# ECG_max86150_v1_7.net
KiCad netlist of a schematic drawn in EAGLE
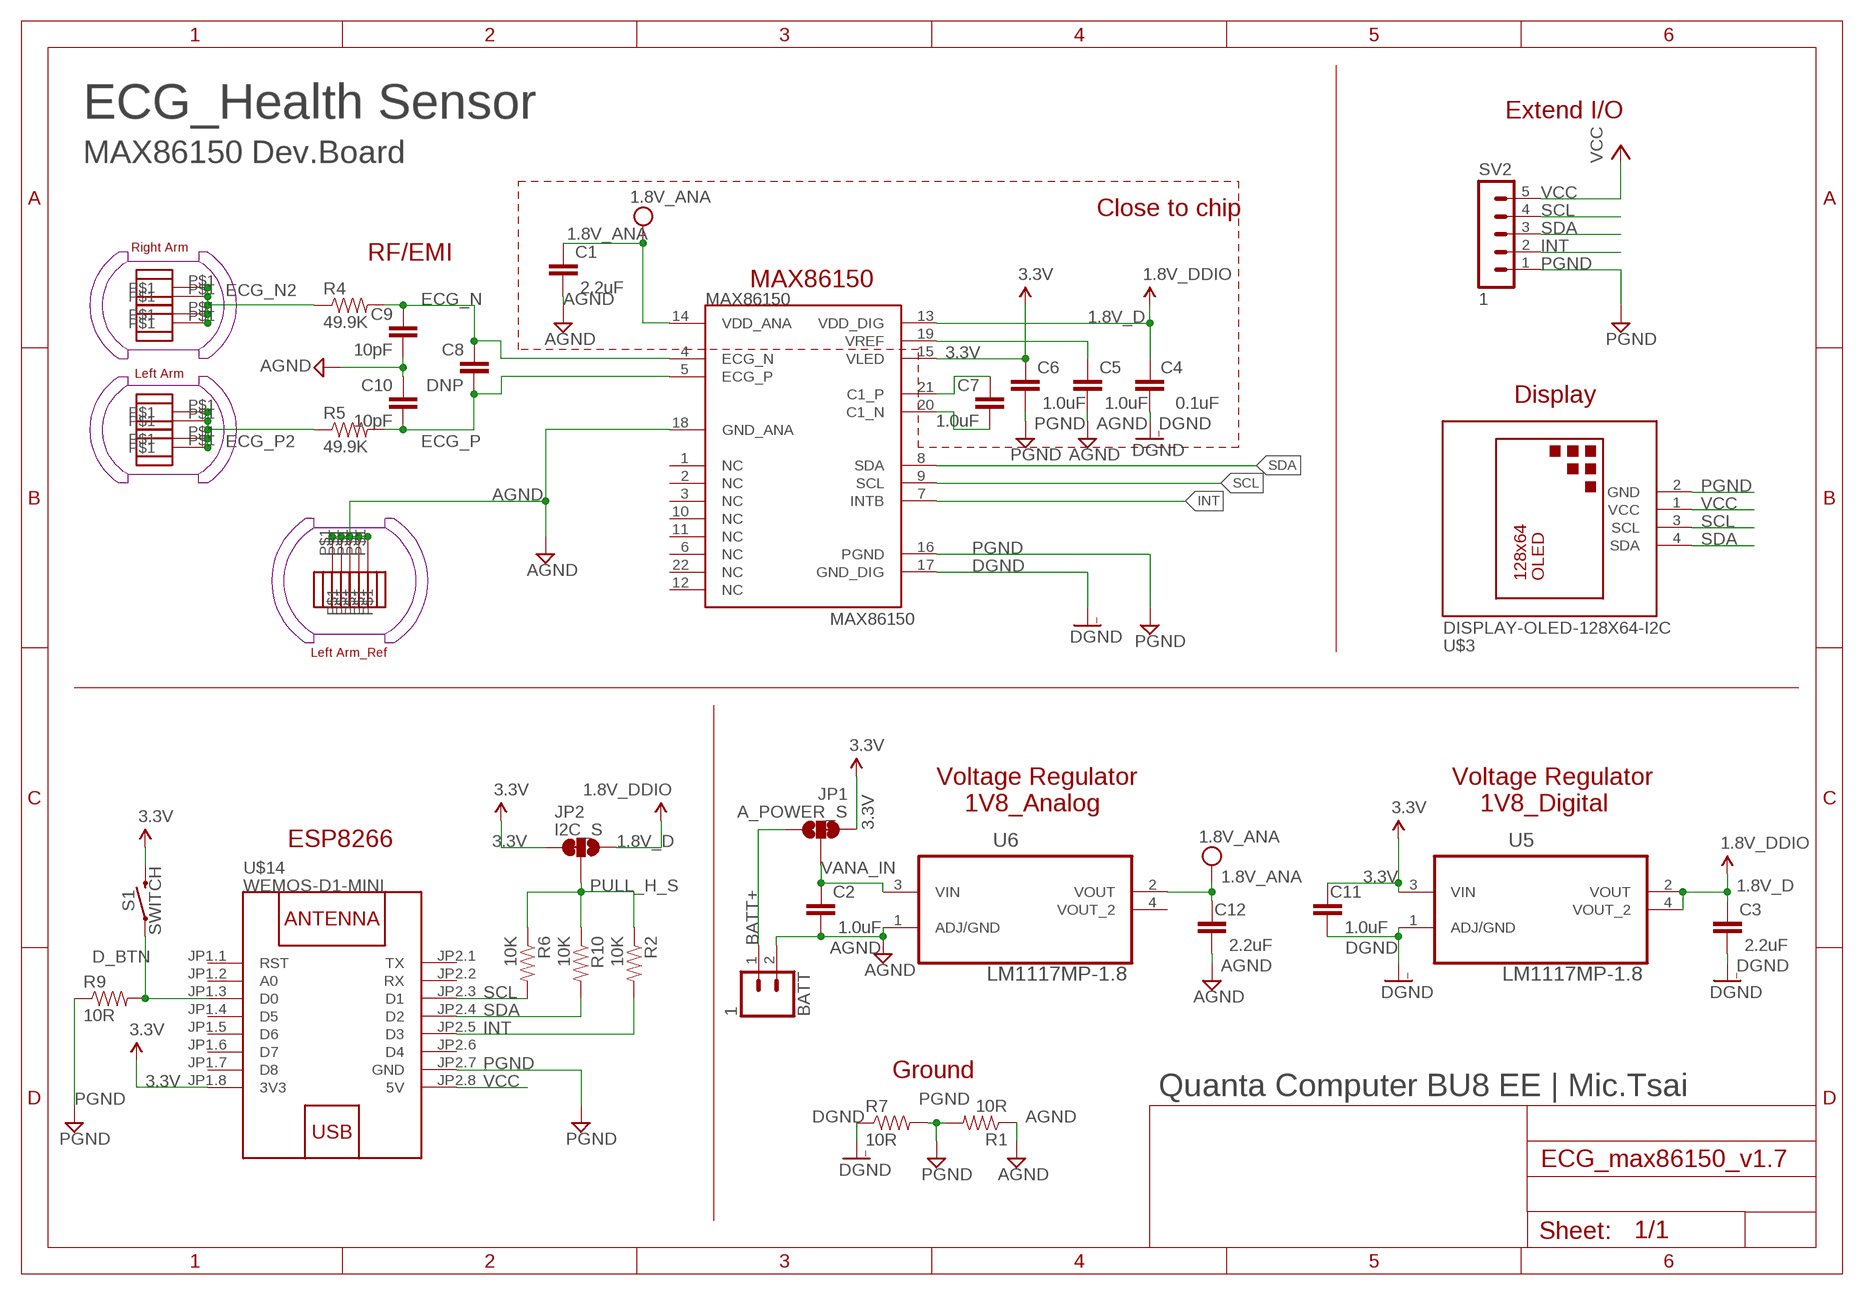
[diagram p0: schematic, sheet 1]

(export (version "E")
  (design (tool "Eeschema 10.0.6"))
  (components
    (comp (ref "BATT")
      (value "1")
      (footprint "eagle-import:1X02")
      (libsource (lib "eagle-import") (part "CONN_02"))
    )
    (comp (ref "C1")
      (value "2.2uF")
      (footprint "eagle-import:0805")
      (libsource (lib "eagle-import") (part "1.0UF-0805-25V-10%"))
    )
    (comp (ref "C2")
      (value "1.0uF")
      (footprint "eagle-import:0805")
      (libsource (lib "eagle-import") (part "1.0UF-0805-25V-10%"))
    )
    (comp (ref "C3")
      (value "2.2uF")
      (footprint "eagle-import:0805")
      (libsource (lib "eagle-import") (part "1.0UF-0805-25V-10%"))
    )
    (comp (ref "C4")
      (value "0.1uF")
      (footprint "eagle-import:0402")
      (libsource (lib "eagle-import") (part "1.0UF-0402-16V-10%"))
    )
    (comp (ref "C5")
      (value "1.0uF")
      (footprint "eagle-import:0805")
      (libsource (lib "eagle-import") (part "1.0UF-0805-25V-10%"))
    )
    (comp (ref "C6")
      (value "1.0uF")
      (footprint "eagle-import:0805")
      (libsource (lib "eagle-import") (part "1.0UF-0805-25V-10%"))
    )
    (comp (ref "C7")
      (value "1.0uF")
      (footprint "eagle-import:0805")
      (libsource (lib "eagle-import") (part "1.0UF-0805-25V-10%"))
    )
    (comp (ref "C8")
      (value "DNP")
      (footprint "eagle-import:0402")
      (libsource (lib "eagle-import") (part "1.0UF-0402-16V-10%"))
    )
    (comp (ref "C9")
      (value "10pF")
      (footprint "eagle-import:0402")
      (libsource (lib "eagle-import") (part "1.0UF-0402-16V-10%"))
    )
    (comp (ref "C10")
      (value "10pF")
      (footprint "eagle-import:0402")
      (libsource (lib "eagle-import") (part "1.0UF-0402-16V-10%"))
    )
    (comp (ref "C11")
      (value "1.0uF")
      (footprint "eagle-import:0805")
      (libsource (lib "eagle-import") (part "1.0UF-0805-25V-10%"))
    )
    (comp (ref "C12")
      (value "2.2uF")
      (footprint "eagle-import:0805")
      (libsource (lib "eagle-import") (part "1.0UF-0805-25V-10%"))
    )
    (comp (ref "JP1")
      (value "A_POWER_S")
      (footprint "eagle-import:SMT-JUMPER_3_1-NC_TRACE_SILK")
      (libsource (lib "eagle-import") (part "JUMPER-SMT_3_1-NC_TRACE_SILK"))
    )
    (comp (ref "JP2")
      (value "I2C_S")
      (footprint "eagle-import:SMT-JUMPER_3_1-NC_TRACE_SILK")
      (libsource (lib "eagle-import") (part "JUMPER-SMT_3_1-NC_TRACE_SILK"))
    )
    (comp (ref "MAX86150")
      (value "MAX86150")
      (footprint "eagle-import:MAX86150")
      (libsource (lib "eagle-import") (part "MAX86150"))
    )
    (comp (ref "R1")
      (value "10R")
      (footprint "eagle-import:0805")
      (libsource (lib "eagle-import") (part "RESISTOR0805-RES"))
    )
    (comp (ref "R2")
      (value "10K")
      (footprint "eagle-import:0402-RES")
      (libsource (lib "eagle-import") (part "RESISTOR0402-RES"))
    )
    (comp (ref "R4")
      (value "49.9K")
      (footprint "eagle-import:0402-RES")
      (libsource (lib "eagle-import") (part "RESISTOR0402-RES"))
    )
    (comp (ref "R5")
      (value "49.9K")
      (footprint "eagle-import:0402-RES")
      (libsource (lib "eagle-import") (part "RESISTOR0402-RES"))
    )
    (comp (ref "R6")
      (value "10K")
      (footprint "eagle-import:0402-RES")
      (libsource (lib "eagle-import") (part "RESISTOR0402-RES"))
    )
    (comp (ref "R7")
      (value "10R")
      (footprint "eagle-import:0805")
      (libsource (lib "eagle-import") (part "RESISTOR0805-RES"))
    )
    (comp (ref "R9")
      (value "10R")
      (footprint "eagle-import:0805")
      (libsource (lib "eagle-import") (part "RESISTOR0805-RES"))
    )
    (comp (ref "R10")
      (value "10K")
      (footprint "eagle-import:0402-RES")
      (libsource (lib "eagle-import") (part "RESISTOR0402-RES"))
    )
    (comp (ref "S1")
      (value "SWITCH")
      (footprint "eagle-import:TACTILE_SWITCH_PTH_6.0MM")
      (libsource (lib "eagle-import") (part "MOMENTARY-SWITCH-SPST-PTH-6.0MM"))
    )
    (comp (ref "SV2")
      (value "1")
      (footprint "eagle-import:MA05-1")
      (libsource (lib "eagle-import") (part "MA05-1"))
    )
    (comp (ref "U$1")
      (value "ECG_PAD")
      (footprint "eagle-import:ECG_PAD1")
      (libsource (lib "eagle-import") (part "ECG_PAD"))
    )
    (comp (ref "U$3")
      (value "DISPLAY-OLED-128X64-I2C")
      (footprint "eagle-import:DISPLAY-OLED-128X64-I2C")
      (libsource (lib "eagle-import") (part "DISPLAY-OLED-128X64-I2C"))
    )
    (comp (ref "U$4")
      (value "ECG_PAD")
      (footprint "eagle-import:ECG_PAD1")
      (libsource (lib "eagle-import") (part "ECG_PAD"))
    )
    (comp (ref "U$6")
      (value "ECG_PAD")
      (footprint "eagle-import:ECG_PAD1")
      (libsource (lib "eagle-import") (part "ECG_PAD"))
    )
    (comp (ref "U$7")
      (value "ECG_PAD")
      (footprint "eagle-import:ECG_PAD1")
      (libsource (lib "eagle-import") (part "ECG_PAD"))
    )
    (comp (ref "U$9")
      (value "ECG_PAD")
      (footprint "eagle-import:ECG_PAD1")
      (libsource (lib "eagle-import") (part "ECG_PAD"))
    )
    (comp (ref "U$10")
      (value "ECG_PAD")
      (footprint "eagle-import:ECG_PAD1")
      (libsource (lib "eagle-import") (part "ECG_PAD"))
    )
    (comp (ref "U$11")
      (value "ECG_PAD")
      (footprint "eagle-import:ECG_PAD1")
      (libsource (lib "eagle-import") (part "ECG_PAD"))
    )
    (comp (ref "U$12")
      (value "ECG_PAD")
      (footprint "eagle-import:ECG_PAD1")
      (libsource (lib "eagle-import") (part "ECG_PAD"))
    )
    (comp (ref "U$13")
      (value "ECG_PAD")
      (footprint "eagle-import:ECG_PAD1")
      (libsource (lib "eagle-import") (part "ECG_PAD"))
    )
    (comp (ref "U$14")
      (value "WEMOS-D1-MINI")
      (footprint "eagle-import:WEMOS-D1-MINI")
      (libsource (lib "eagle-import") (part "WEMOS-D1-MINI"))
    )
    (comp (ref "U$15")
      (value "ECG_PAD")
      (footprint "eagle-import:ECG_PAD1")
      (libsource (lib "eagle-import") (part "ECG_PAD"))
    )
    (comp (ref "U$16")
      (value "ECG_PAD")
      (footprint "eagle-import:ECG_PAD1")
      (libsource (lib "eagle-import") (part "ECG_PAD"))
    )
    (comp (ref "U$17")
      (value "ECG_PAD")
      (footprint "eagle-import:ECG_PAD1")
      (libsource (lib "eagle-import") (part "ECG_PAD"))
    )
    (comp (ref "U$18")
      (value "ECG_PAD")
      (footprint "eagle-import:ECG_PAD1")
      (libsource (lib "eagle-import") (part "ECG_PAD"))
    )
    (comp (ref "U5")
      (value "LM1117MP-1.8")
      (footprint "eagle-import:SOT230P696X180-4N")
      (fields (field (name "MF") "Texas Instruments") (field (name "MP") "LM1117MP-1.8/NOPB"))
      (libsource (lib "eagle-import") (part "LM1117MP-1.8"))
    )
    (comp (ref "U6")
      (value "LM1117MP-1.8")
      (footprint "eagle-import:SOT230P696X180-4N")
      (fields (field (name "MF") "Texas Instruments") (field (name "MP") "LM1117MP-1.8/NOPB"))
      (libsource (lib "eagle-import") (part "LM1117MP-1.8"))
    )
  )
  (nets
    (net (code "1") (name "/BATT+") (class "Default")
      (node (ref "BATT") (pin "1") (pinfunction "1_1") (pintype "passive"))
      (node (ref "JP1") (pin "1") (pinfunction "1_1") (pintype "passive"))
    )
    (net (code "2") (name "/D_BTN") (class "Default")
      (node (ref "R9") (pin "2") (pinfunction "2_2") (pintype "passive"))
      (node (ref "S1") (pin "1") (pinfunction "1_1") (pintype "passive"))
      (node (ref "U$14") (pin "JP1.3") (pinfunction "D0_JP1.3") (pintype "bidirectional"))
    )
    (net (code "3") (name "/ECG_N") (class "Default")
      (node (ref "C8") (pin "1") (pinfunction "1_1") (pintype "passive"))
      (node (ref "C9") (pin "1") (pinfunction "1_1") (pintype "passive"))
      (node (ref "MAX86150") (pin "4") (pinfunction "ECG_N_4") (pintype "bidirectional"))
      (node (ref "R4") (pin "2") (pinfunction "2_2") (pintype "passive"))
    )
    (net (code "4") (name "/ECG_N2") (class "Default")
      (node (ref "R4") (pin "1") (pinfunction "1_1") (pintype "passive"))
      (node (ref "U$10") (pin "P$1") (pinfunction "P$1_P$1") (pintype "bidirectional"))
      (node (ref "U$11") (pin "P$1") (pinfunction "P$1_P$1") (pintype "bidirectional"))
      (node (ref "U$16") (pin "P$1") (pinfunction "P$1_P$1") (pintype "bidirectional"))
      (node (ref "U$9") (pin "P$1") (pinfunction "P$1_P$1") (pintype "bidirectional"))
    )
    (net (code "5") (name "/ECG_P") (class "Default")
      (node (ref "C10") (pin "2") (pinfunction "2_2") (pintype "passive"))
      (node (ref "C8") (pin "2") (pinfunction "2_2") (pintype "passive"))
      (node (ref "MAX86150") (pin "5") (pinfunction "ECG_P_5") (pintype "bidirectional"))
      (node (ref "R5") (pin "2") (pinfunction "2_2") (pintype "passive"))
    )
    (net (code "6") (name "/ECG_P2") (class "Default")
      (node (ref "R5") (pin "1") (pinfunction "1_1") (pintype "passive"))
      (node (ref "U$1") (pin "P$1") (pinfunction "P$1_P$1") (pintype "bidirectional"))
      (node (ref "U$4") (pin "P$1") (pinfunction "P$1_P$1") (pintype "bidirectional"))
      (node (ref "U$6") (pin "P$1") (pinfunction "P$1_P$1") (pintype "bidirectional"))
      (node (ref "U$7") (pin "P$1") (pinfunction "P$1_P$1") (pintype "bidirectional"))
    )
    (net (code "7") (name "/PULL_H_S") (class "Default")
      (node (ref "JP2") (pin "2") (pinfunction "2_2") (pintype "passive"))
      (node (ref "R10") (pin "1") (pinfunction "1_1") (pintype "passive"))
      (node (ref "R2") (pin "1") (pinfunction "1_1") (pintype "passive"))
      (node (ref "R6") (pin "1") (pinfunction "1_1") (pintype "passive"))
    )
    (net (code "8") (name "/VANA_IN") (class "Default")
      (node (ref "C2") (pin "1") (pinfunction "1_1") (pintype "passive"))
      (node (ref "JP1") (pin "2") (pinfunction "2_2") (pintype "passive"))
      (node (ref "U6") (pin "3") (pinfunction "VIN_3") (pintype "input"))
    )
    (net (code "9") (name "1.8V_ANA") (class "Default")
      (node (ref "C1") (pin "1") (pinfunction "1_1") (pintype "passive"))
      (node (ref "C12") (pin "1") (pinfunction "1_1") (pintype "passive"))
      (node (ref "MAX86150") (pin "14") (pinfunction "VDD_ANA_14") (pintype "bidirectional"))
      (node (ref "U6") (pin "2") (pinfunction "VOUT_2") (pintype "output"))
    )
    (net (code "10") (name "1.8V_DDIO") (class "Default")
      (node (ref "C3") (pin "1") (pinfunction "1_1") (pintype "passive"))
      (node (ref "C4") (pin "1") (pinfunction "1_1") (pintype "passive"))
      (node (ref "JP2") (pin "1") (pinfunction "1_1") (pintype "passive"))
      (node (ref "MAX86150") (pin "13") (pinfunction "VDD_DIG_13") (pintype "bidirectional"))
      (node (ref "U5") (pin "2") (pinfunction "VOUT_2") (pintype "output"))
      (node (ref "U5") (pin "4") (pinfunction "VOUT_2_4") (pintype "output"))
    )
    (net (code "11") (name "3.3V") (class "Default")
      (node (ref "C11") (pin "1") (pinfunction "1_1") (pintype "passive"))
      (node (ref "C6") (pin "1") (pinfunction "1_1") (pintype "passive"))
      (node (ref "JP1") (pin "3") (pinfunction "3_3") (pintype "passive"))
      (node (ref "JP2") (pin "3") (pinfunction "3_3") (pintype "passive"))
      (node (ref "MAX86150") (pin "15") (pinfunction "VLED_15") (pintype "bidirectional"))
      (node (ref "S1") (pin "3") (pinfunction "2_3") (pintype "passive"))
      (node (ref "U$14") (pin "JP1.8") (pinfunction "3V3_JP1.8") (pintype "power_in"))
      (node (ref "U5") (pin "3") (pinfunction "VIN_3") (pintype "input"))
    )
    (net (code "12") (name "AGND") (class "Default")
      (node (ref "BATT") (pin "2") (pinfunction "2_2") (pintype "passive"))
      (node (ref "C1") (pin "2") (pinfunction "2_2") (pintype "passive"))
      (node (ref "C10") (pin "1") (pinfunction "1_1") (pintype "passive"))
      (node (ref "C12") (pin "2") (pinfunction "2_2") (pintype "passive"))
      (node (ref "C2") (pin "2") (pinfunction "2_2") (pintype "passive"))
      (node (ref "C5") (pin "2") (pinfunction "2_2") (pintype "passive"))
      (node (ref "C9") (pin "2") (pinfunction "2_2") (pintype "passive"))
      (node (ref "MAX86150") (pin "18") (pinfunction "GND_ANA_18") (pintype "bidirectional"))
      (node (ref "R1") (pin "1") (pinfunction "1_1") (pintype "passive"))
      (node (ref "U$12") (pin "P$1") (pinfunction "P$1_P$1") (pintype "bidirectional"))
      (node (ref "U$13") (pin "P$1") (pinfunction "P$1_P$1") (pintype "bidirectional"))
      (node (ref "U$15") (pin "P$1") (pinfunction "P$1_P$1") (pintype "bidirectional"))
      (node (ref "U$17") (pin "P$1") (pinfunction "P$1_P$1") (pintype "bidirectional"))
      (node (ref "U$18") (pin "P$1") (pinfunction "P$1_P$1") (pintype "bidirectional"))
      (node (ref "U6") (pin "1") (pinfunction "ADJ/GND_1") (pintype "passive"))
    )
    (net (code "13") (name "DGND") (class "Default")
      (node (ref "C11") (pin "2") (pinfunction "2_2") (pintype "passive"))
      (node (ref "C3") (pin "2") (pinfunction "2_2") (pintype "passive"))
      (node (ref "C4") (pin "2") (pinfunction "2_2") (pintype "passive"))
      (node (ref "MAX86150") (pin "17") (pinfunction "GND_DIG_17") (pintype "bidirectional"))
      (node (ref "R7") (pin "1") (pinfunction "1_1") (pintype "passive"))
      (node (ref "U5") (pin "1") (pinfunction "ADJ/GND_1") (pintype "passive"))
    )
    (net (code "14") (name "INT") (class "Default")
      (node (ref "MAX86150") (pin "7") (pinfunction "INTB_7") (pintype "bidirectional"))
      (node (ref "R2") (pin "2") (pinfunction "2_2") (pintype "passive"))
      (node (ref "SV2") (pin "2") (pinfunction "2_2") (pintype "passive"))
      (node (ref "U$14") (pin "JP2.5") (pinfunction "D3_JP2.5") (pintype "bidirectional"))
    )
    (net (code "15") (name "Net-(MAX86150-C1_N)") (class "Default")
      (node (ref "C7") (pin "2") (pinfunction "2_2") (pintype "passive"))
      (node (ref "MAX86150") (pin "20") (pinfunction "C1_N_20") (pintype "bidirectional"))
    )
    (net (code "16") (name "Net-(MAX86150-C1_P)") (class "Default")
      (node (ref "C7") (pin "1") (pinfunction "1_1") (pintype "passive"))
      (node (ref "MAX86150") (pin "21") (pinfunction "C1_P_21") (pintype "bidirectional"))
    )
    (net (code "17") (name "Net-(MAX86150-VREF)") (class "Default")
      (node (ref "C5") (pin "1") (pinfunction "1_1") (pintype "passive"))
      (node (ref "MAX86150") (pin "19") (pinfunction "VREF_19") (pintype "bidirectional"))
    )
    (net (code "18") (name "PGND") (class "Default")
      (node (ref "C6") (pin "2") (pinfunction "2_2") (pintype "passive"))
      (node (ref "MAX86150") (pin "16") (pinfunction "PGND_16") (pintype "bidirectional"))
      (node (ref "R1") (pin "2") (pinfunction "2_2") (pintype "passive"))
      (node (ref "R7") (pin "2") (pinfunction "2_2") (pintype "passive"))
      (node (ref "R9") (pin "1") (pinfunction "1_1") (pintype "passive"))
      (node (ref "SV2") (pin "1") (pinfunction "1_1") (pintype "passive"))
      (node (ref "U$14") (pin "JP2.7") (pinfunction "GND_JP2.7") (pintype "power_in"))
      (node (ref "U$3") (pin "2") (pinfunction "GND_2") (pintype "power_in"))
    )
    (net (code "19") (name "SCL") (class "Default")
      (node (ref "MAX86150") (pin "9") (pinfunction "SCL_9") (pintype "bidirectional"))
      (node (ref "R6") (pin "2") (pinfunction "2_2") (pintype "passive"))
      (node (ref "SV2") (pin "4") (pinfunction "4_4") (pintype "passive"))
      (node (ref "U$14") (pin "JP2.3") (pinfunction "D1_JP2.3") (pintype "bidirectional"))
      (node (ref "U$3") (pin "3") (pinfunction "SCL_3") (pintype "bidirectional"))
    )
    (net (code "20") (name "SDA") (class "Default")
      (node (ref "MAX86150") (pin "8") (pinfunction "SDA_8") (pintype "bidirectional"))
      (node (ref "R10") (pin "2") (pinfunction "2_2") (pintype "passive"))
      (node (ref "SV2") (pin "3") (pinfunction "3_3") (pintype "passive"))
      (node (ref "U$14") (pin "JP2.4") (pinfunction "D2_JP2.4") (pintype "bidirectional"))
      (node (ref "U$3") (pin "4") (pinfunction "SDA_4") (pintype "bidirectional"))
    )
    (net (code "21") (name "VCC") (class "Default")
      (node (ref "SV2") (pin "5") (pinfunction "5_5") (pintype "passive"))
      (node (ref "U$14") (pin "JP2.8") (pinfunction "5V_JP2.8") (pintype "power_in"))
      (node (ref "U$3") (pin "1") (pinfunction "VCC_1") (pintype "power_in"))
    )
    (net (code "22") (name "unconnected-(MAX86150-NC-Pad1)") (class "Default")
      (node (ref "MAX86150") (pin "1") (pinfunction "NC_1") (pintype "bidirectional"))
    )
    (net (code "23") (name "unconnected-(MAX86150-NC-Pad2)") (class "Default")
      (node (ref "MAX86150") (pin "2") (pinfunction "NC_2") (pintype "bidirectional"))
    )
    (net (code "24") (name "unconnected-(MAX86150-NC-Pad3)") (class "Default")
      (node (ref "MAX86150") (pin "3") (pinfunction "NC_3") (pintype "bidirectional"))
    )
    (net (code "25") (name "unconnected-(MAX86150-NC-Pad6)") (class "Default")
      (node (ref "MAX86150") (pin "6") (pinfunction "NC_6") (pintype "bidirectional"))
    )
    (net (code "26") (name "unconnected-(MAX86150-NC-Pad10)") (class "Default")
      (node (ref "MAX86150") (pin "10") (pinfunction "NC_10") (pintype "bidirectional"))
    )
    (net (code "27") (name "unconnected-(MAX86150-NC-Pad11)") (class "Default")
      (node (ref "MAX86150") (pin "11") (pinfunction "NC_11") (pintype "bidirectional"))
    )
    (net (code "28") (name "unconnected-(MAX86150-NC-Pad12)") (class "Default")
      (node (ref "MAX86150") (pin "12") (pinfunction "NC_12") (pintype "bidirectional"))
    )
    (net (code "29") (name "unconnected-(MAX86150-NC-Pad22)") (class "Default")
      (node (ref "MAX86150") (pin "22") (pinfunction "NC_22") (pintype "bidirectional"))
    )
    (net (code "30") (name "unconnected-(U$14-A0-PadJP1.2)") (class "Default")
      (node (ref "U$14") (pin "JP1.2") (pinfunction "A0_JP1.2") (pintype "bidirectional"))
    )
    (net (code "31") (name "unconnected-(U$14-D4-PadJP2.6)") (class "Default")
      (node (ref "U$14") (pin "JP2.6") (pinfunction "D4_JP2.6") (pintype "bidirectional"))
    )
    (net (code "32") (name "unconnected-(U$14-D5-PadJP1.4)") (class "Default")
      (node (ref "U$14") (pin "JP1.4") (pinfunction "D5_JP1.4") (pintype "bidirectional"))
    )
    (net (code "33") (name "unconnected-(U$14-D6-PadJP1.5)") (class "Default")
      (node (ref "U$14") (pin "JP1.5") (pinfunction "D6_JP1.5") (pintype "bidirectional"))
    )
    (net (code "34") (name "unconnected-(U$14-D7-PadJP1.6)") (class "Default")
      (node (ref "U$14") (pin "JP1.6") (pinfunction "D7_JP1.6") (pintype "bidirectional"))
    )
    (net (code "35") (name "unconnected-(U$14-D8-PadJP1.7)") (class "Default")
      (node (ref "U$14") (pin "JP1.7") (pinfunction "D8_JP1.7") (pintype "bidirectional"))
    )
    (net (code "36") (name "unconnected-(U$14-RST-PadJP1.1)") (class "Default")
      (node (ref "U$14") (pin "JP1.1") (pinfunction "RST_JP1.1") (pintype "bidirectional"))
    )
    (net (code "37") (name "unconnected-(U$14-RX-PadJP2.2)") (class "Default")
      (node (ref "U$14") (pin "JP2.2") (pinfunction "RX_JP2.2") (pintype "bidirectional"))
    )
    (net (code "38") (name "unconnected-(U$14-TX-PadJP2.1)") (class "Default")
      (node (ref "U$14") (pin "JP2.1") (pinfunction "TX_JP2.1") (pintype "bidirectional"))
    )
    (net (code "39") (name "unconnected-(U6-VOUT_2-Pad4)") (class "Default")
      (node (ref "U6") (pin "4") (pinfunction "VOUT_2_4") (pintype "output"))
    )
  )
)
